# Safety_Thermocouple_Interface_-_MCU.net
KiCad netlist of a schematic drawn in Altium Designer
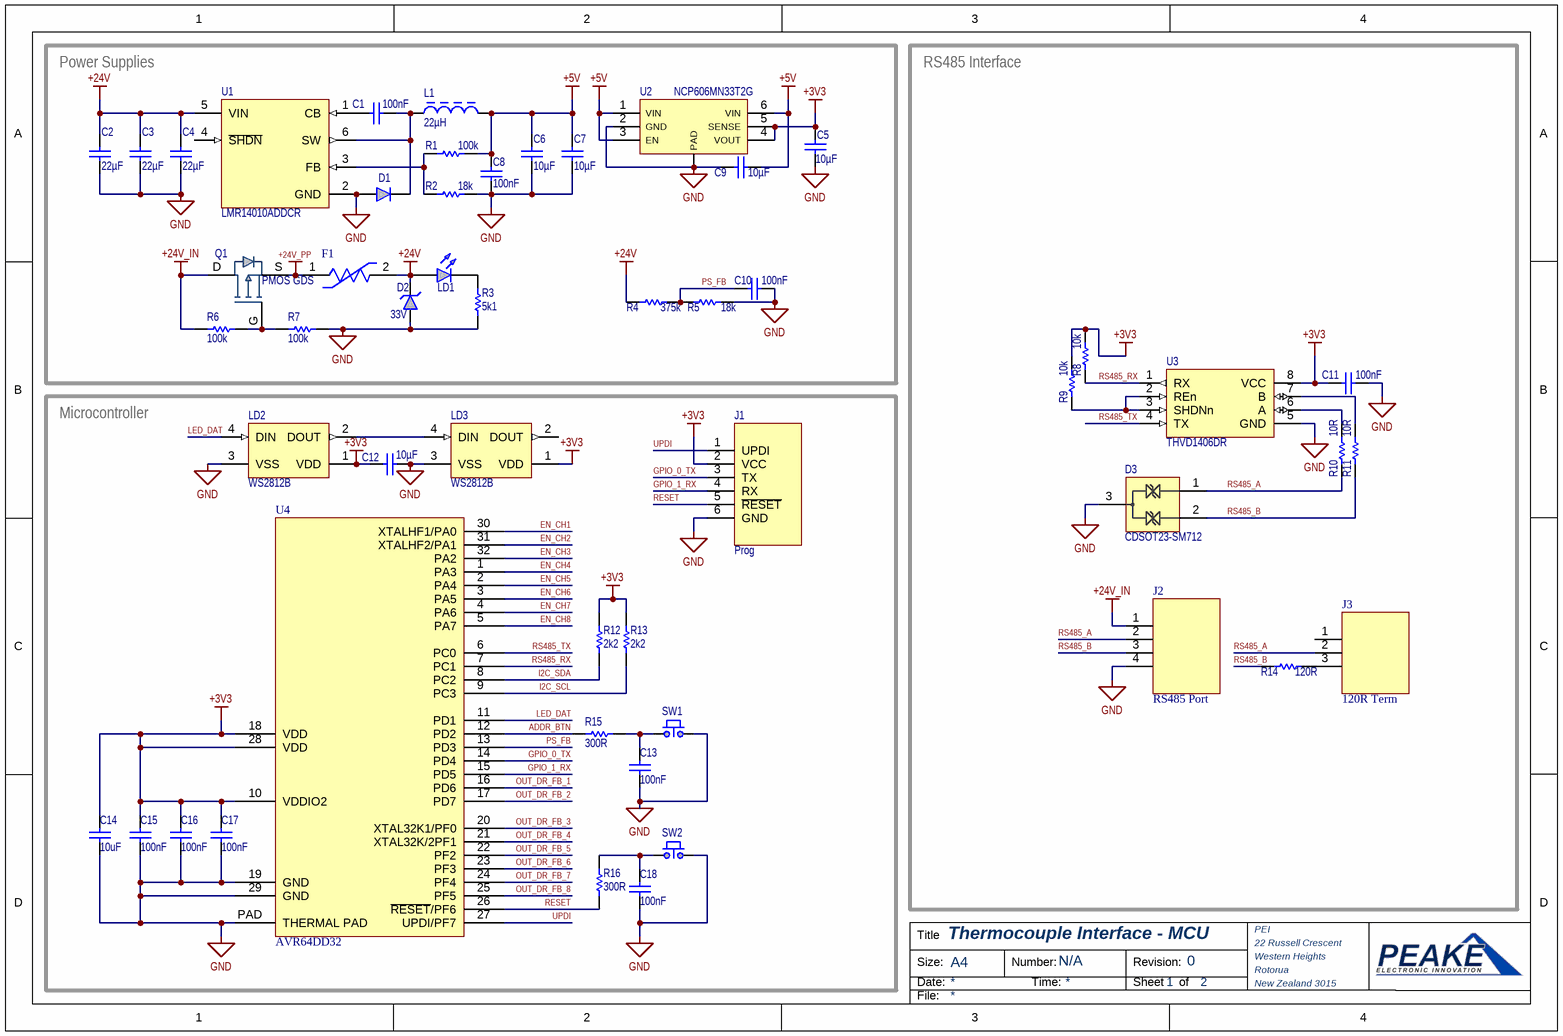
[diagram p0: Safety Thermocouple Interface - MCU.SchDoc]

(export (version "E")
  (design (tool "Eeschema 10.0.6"))
  (components
    (comp (ref "C1")
      (value "100nF")
      (footprint "0603_CAP")
      (description "SMD Capacitor")
      (fields (field (name "Comment") "Capacitor"))
      (libsource (lib "Scion Research") (part "CMP-019-00005-2"))
    )
    (comp (ref "C2")
      (value "22µF")
      (footprint "1206_CAP")
      (description "SMD Capacitor")
      (fields (field (name "Comment") "Capacitor"))
      (libsource (lib "Scion Research") (part "CMP-019-00005-2"))
    )
    (comp (ref "C3")
      (value "22µF")
      (footprint "1206_CAP")
      (description "SMD Capacitor")
      (fields (field (name "Comment") "Capacitor"))
      (libsource (lib "Scion Research") (part "CMP-019-00005-2"))
    )
    (comp (ref "C4")
      (value "22µF")
      (footprint "1206_CAP")
      (description "SMD Capacitor")
      (fields (field (name "Comment") "Capacitor"))
      (libsource (lib "Scion Research") (part "CMP-019-00005-2"))
    )
    (comp (ref "C5")
      (value "10µF")
      (footprint "0603_CAP")
      (description "SMD Capacitor")
      (fields (field (name "Comment") "Capacitor"))
      (libsource (lib "Scion Research") (part "CMP-019-00005-2"))
    )
    (comp (ref "C6")
      (value "10µF")
      (footprint "0603_CAP")
      (description "SMD Capacitor")
      (fields (field (name "Comment") "Capacitor"))
      (libsource (lib "Scion Research") (part "CMP-019-00005-2"))
    )
    (comp (ref "C7")
      (value "10µF")
      (footprint "0603_CAP")
      (description "SMD Capacitor")
      (fields (field (name "Comment") "Capacitor"))
      (libsource (lib "Scion Research") (part "CMP-019-00005-2"))
    )
    (comp (ref "C8")
      (value "100nF")
      (footprint "0603_CAP")
      (description "SMD Capacitor")
      (fields (field (name "Comment") "Capacitor"))
      (libsource (lib "Scion Research") (part "CMP-019-00005-2"))
    )
    (comp (ref "C9")
      (value "10µF")
      (footprint "0603_CAP")
      (description "SMD Capacitor")
      (fields (field (name "Comment") "Capacitor"))
      (libsource (lib "Scion Research") (part "CMP-019-00005-2"))
    )
    (comp (ref "C10")
      (value "100nF")
      (footprint "0603_CAP")
      (description "SMD Capacitor")
      (fields (field (name "Comment") "Capacitor"))
      (libsource (lib "Scion Research") (part "CMP-019-00005-2"))
    )
    (comp (ref "C11")
      (value "100nF")
      (footprint "0603_CAP")
      (description "SMD Capacitor")
      (fields (field (name "Comment") "Capacitor"))
      (libsource (lib "Scion Research") (part "CMP-019-00005-2"))
    )
    (comp (ref "C12")
      (value "10µF")
      (footprint "0603_CAP")
      (description "SMD Capacitor")
      (fields (field (name "Comment") "Capacitor"))
      (libsource (lib "Scion Research") (part "CMP-019-00005-2"))
    )
    (comp (ref "C13")
      (value "100nF")
      (footprint "0603_CAP")
      (description "SMD Capacitor")
      (fields (field (name "Comment") "Capacitor"))
      (libsource (lib "Scion Research") (part "CMP-019-00005-2"))
    )
    (comp (ref "C14")
      (value "10uF")
      (footprint "0603_CAP")
      (description "SMD Capacitor")
      (fields (field (name "Comment") "Capacitor"))
      (libsource (lib "Scion Research") (part "CMP-019-00005-2"))
    )
    (comp (ref "C15")
      (value "100nF")
      (footprint "0603_CAP")
      (description "SMD Capacitor")
      (fields (field (name "Comment") "Capacitor"))
      (libsource (lib "Scion Research") (part "CMP-019-00005-2"))
    )
    (comp (ref "C16")
      (value "100nF")
      (footprint "0603_CAP")
      (description "SMD Capacitor")
      (fields (field (name "Comment") "Capacitor"))
      (libsource (lib "Scion Research") (part "CMP-019-00005-2"))
    )
    (comp (ref "C17")
      (value "100nF")
      (footprint "0603_CAP")
      (description "SMD Capacitor")
      (fields (field (name "Comment") "Capacitor"))
      (libsource (lib "Scion Research") (part "CMP-019-00005-2"))
    )
    (comp (ref "C18")
      (value "100nF")
      (footprint "0603_CAP")
      (description "SMD Capacitor")
      (fields (field (name "Comment") "Capacitor"))
      (libsource (lib "Scion Research") (part "CMP-019-00005-2"))
    )
    (comp (ref "D1")
      (value "Diode")
      (footprint "SOD-123")
      (description "SMD Diode")
      (libsource (lib "Scion Research") (part "Diode"))
    )
    (comp (ref "D2")
      (value "Transil")
      (footprint "SMBJ")
      (description "Transient Voltage Suppressor")
      (fields (field (name "RATED VOLTAGE") "33V"))
      (libsource (lib "Scion Research") (part "CMP-004-0042-1"))
    )
    (comp (ref "D3")
      (value "CDSOT23-SM712")
      (footprint "FP-SOT23-IPC_C")
      (description "Trans Voltage Suppressor Diode, 400W, 7V V(RWM), Bidirectional, 2 Element, Silicon")
      (libsource (lib "Scion Research") (part "CDSOT23-SM712"))
    )
    (comp (ref "F1")
      (value "0ZCF0100AF2A")
      (footprint "FP-0ZCF0100AF2A-MFG")
      (description "PTC Resettable Fuse 100A 0.5s 60VDC 0.09 Ohm 2-Pin 2920 T/R")
      (libsource (lib "Scion Research") (part "CMP-00051-1"))
    )
    (comp (ref "J1")
      (value "Prog")
      (footprint "DIP6")
      (description "6 Pin Connector")
      (libsource (lib "Scion Research") (part "CMP-002-00081-5"))
    )
    (comp (ref "J2")
      (value "RS485 Port")
      (footprint "4_Pin  DB2EVC-3.81-4P-GN LCSC version")
      (description "4 Pin Connector")
      (libsource (lib "Scion Research") (part "CMP-002-00078-6"))
    )
    (comp (ref "J3")
      (value "120R Term")
      (footprint "SIP3")
      (description "3 Pin Connector")
      (libsource (lib "Scion Research") (part "CMP-002-00075-6"))
    )
    (comp (ref "L1")
      (value "22µH")
      (footprint "BOUR-SRN8040_V")
      (description "Power Inductor")
      (fields (field (name "Comment") "Inductor"))
      (libsource (lib "Scion Research") (part "Inductor"))
    )
    (comp (ref "LD1")
      (value "LED")
      (footprint "0805")
      (description "SMD LED")
      (libsource (lib "Scion Research") (part "CMP-004-00032-1"))
    )
    (comp (ref "LD2")
      (value "WS2812B")
      (footprint "WS2812B-2020")
      (fields (field (name "MANUFACTURER") "Adafruit Industries"))
      (libsource (lib "Scion Research") (part "CMP-007-00035-3"))
    )
    (comp (ref "LD3")
      (value "WS2812B")
      (footprint "WS2812B-2020")
      (fields (field (name "MANUFACTURER") "Adafruit Industries"))
      (libsource (lib "Scion Research") (part "CMP-007-00035-3"))
    )
    (comp (ref "Q1")
      (value "PMOS GDS")
      (footprint "PowerDI 5060-8")
      (description "P Channel MOSFET")
      (libsource (lib "Scion Research") (part "CMP-004-0035-2"))
    )
    (comp (ref "R1")
      (value "Resistor")
      (footprint "0603_RES")
      (description "SMD Resistor")
      (fields (field (name "ALTIUM_VALUE") "100k"))
      (libsource (lib "Scion Research") (part "CMP-009-00177-2"))
    )
    (comp (ref "R2")
      (value "Resistor")
      (footprint "0603_RES")
      (description "SMD Resistor")
      (fields (field (name "ALTIUM_VALUE") "18k"))
      (libsource (lib "Scion Research") (part "CMP-009-00177-2"))
    )
    (comp (ref "R3")
      (value "Resistor")
      (footprint "0603_RES")
      (description "SMD Resistor")
      (fields (field (name "ALTIUM_VALUE") "5k1"))
      (libsource (lib "Scion Research") (part "CMP-009-00177-2"))
    )
    (comp (ref "R4")
      (value "Resistor")
      (footprint "0603_RES")
      (description "SMD Resistor")
      (fields (field (name "ALTIUM_VALUE") "375k"))
      (libsource (lib "Scion Research") (part "CMP-009-00177-2"))
    )
    (comp (ref "R5")
      (value "Resistor")
      (footprint "0603_RES")
      (description "SMD Resistor")
      (fields (field (name "ALTIUM_VALUE") "18k"))
      (libsource (lib "Scion Research") (part "CMP-009-00177-2"))
    )
    (comp (ref "R6")
      (value "Resistor")
      (footprint "0603_RES")
      (description "SMD Resistor")
      (fields (field (name "ALTIUM_VALUE") "100k"))
      (libsource (lib "Scion Research") (part "CMP-009-00177-2"))
    )
    (comp (ref "R7")
      (value "Resistor")
      (footprint "0603_RES")
      (description "SMD Resistor")
      (fields (field (name "ALTIUM_VALUE") "100k"))
      (libsource (lib "Scion Research") (part "CMP-009-00177-2"))
    )
    (comp (ref "R8")
      (value "Resistor")
      (footprint "0603_RES")
      (description "SMD Resistor")
      (fields (field (name "ALTIUM_VALUE") "10k"))
      (libsource (lib "Scion Research") (part "CMP-009-00177-2"))
    )
    (comp (ref "R9")
      (value "Resistor")
      (footprint "0603_RES")
      (description "SMD Resistor")
      (fields (field (name "ALTIUM_VALUE") "10k"))
      (libsource (lib "Scion Research") (part "CMP-009-00177-2"))
    )
    (comp (ref "R10")
      (value "Resistor")
      (footprint "0603_RES")
      (description "SMD Resistor")
      (fields (field (name "ALTIUM_VALUE") "10R"))
      (libsource (lib "Scion Research") (part "CMP-009-00177-2"))
    )
    (comp (ref "R11")
      (value "Resistor")
      (footprint "0603_RES")
      (description "SMD Resistor")
      (fields (field (name "ALTIUM_VALUE") "10R"))
      (libsource (lib "Scion Research") (part "CMP-009-00177-2"))
    )
    (comp (ref "R12")
      (value "Resistor")
      (footprint "0603_RES")
      (description "SMD Resistor")
      (fields (field (name "ALTIUM_VALUE") "2k2"))
      (libsource (lib "Scion Research") (part "CMP-009-00177-2"))
    )
    (comp (ref "R13")
      (value "Resistor")
      (footprint "0603_RES")
      (description "SMD Resistor")
      (fields (field (name "ALTIUM_VALUE") "2k2"))
      (libsource (lib "Scion Research") (part "CMP-009-00177-2"))
    )
    (comp (ref "R14")
      (value "Resistor")
      (footprint "0603_RES")
      (description "SMD Resistor")
      (fields (field (name "ALTIUM_VALUE") "120R"))
      (libsource (lib "Scion Research") (part "CMP-009-00177-2"))
    )
    (comp (ref "R15")
      (value "Resistor")
      (footprint "0603_RES")
      (description "SMD Resistor")
      (fields (field (name "ALTIUM_VALUE") "300R"))
      (libsource (lib "Scion Research") (part "CMP-009-00177-2"))
    )
    (comp (ref "R16")
      (value "Resistor")
      (footprint "0603_RES")
      (description "SMD Resistor")
      (fields (field (name "ALTIUM_VALUE") "300R"))
      (libsource (lib "Scion Research") (part "CMP-009-00177-2"))
    )
    (comp (ref "SW1")
      (value "EVP-AAN02Q")
      (footprint "FP-EVP-AAN02Q-MFG")
      (description "Switch Tactile N.O. SPST Rectangular Button J-Bend 0.02A 15VDC 100000Cycles 5N SMD T/R")
      (libsource (lib "Scion Research") (part "67890d47754ac483cb1d3ba3be74b6c"))
    )
    (comp (ref "SW2")
      (value "EVP-AAN02Q")
      (footprint "FP-EVP-AAN02Q-MFG")
      (description "Switch Tactile N.O. SPST Rectangular Button J-Bend 0.02A 15VDC 100000Cycles 5N SMD T/R")
      (libsource (lib "Scion Research") (part "67890d47754ac483cb1d3ba3be74b6c"))
    )
    (comp (ref "U1")
      (value "LMR14010ADDCR")
      (footprint "FP-DDC0006A-IPC_A")
      (description "7-40VDC-DC buck converter")
      (libsource (lib "Scion Research") (part "LMR14010"))
    )
    (comp (ref "U2")
      (value "NCP606MN33T2G")
      (footprint "QFN95P330X295X100_HS-7N")
      (description "Fixed Positive LDO Regulator, 3.3V, 0.22V Dropout, CMOS")
      (libsource (lib "Scion Research") (part "NCP606MN33T2G-Symbol-1"))
    )
    (comp (ref "U3")
      (value "THVD1406DR")
      (footprint "SOIC127P600X175-8N")
      (description "Line Transceiver, 1 Func, 1 Driver, 1 Rcvr, PDSO8")
      (libsource (lib "Scion Research") (part "THVD1406DR-Symbol-1"))
    )
    (comp (ref "U4")
      (value "AVR64DD32")
      (footprint "32P VQFN")
      (libsource (lib "Scion Research") (part "AVR64DD32"))
    )
  )
  (nets
    (net (code "1") (name "+3V3") (class "Default")
      (node (ref "C11") (pin "2") (pinfunction "2_2") (pintype "passive"))
      (node (ref "C12") (pin "2") (pinfunction "2_2") (pintype "passive"))
      (node (ref "C14") (pin "2") (pinfunction "2_2") (pintype "passive"))
      (node (ref "C15") (pin "2") (pinfunction "2_2") (pintype "passive"))
      (node (ref "C16") (pin "2") (pinfunction "2_2") (pintype "passive"))
      (node (ref "C17") (pin "2") (pinfunction "2_2") (pintype "passive"))
      (node (ref "C5") (pin "1") (pinfunction "1_1") (pintype "passive"))
      (node (ref "J1") (pin "2") (pinfunction "VCC_2") (pintype "passive"))
      (node (ref "LD2") (pin "1") (pinfunction "VDD_1") (pintype "power_in"))
      (node (ref "LD3") (pin "1") (pinfunction "VDD_1") (pintype "power_in"))
      (node (ref "R12") (pin "1") (pinfunction "1_1") (pintype "passive"))
      (node (ref "R13") (pin "1") (pinfunction "1_1") (pintype "passive"))
      (node (ref "R8") (pin "1") (pinfunction "1_1") (pintype "passive"))
      (node (ref "R9") (pin "1") (pinfunction "1_1") (pintype "passive"))
      (node (ref "U2") (pin "4") (pinfunction "VOUT_4") (pintype "passive"))
      (node (ref "U2") (pin "5") (pinfunction "SENSE_5") (pintype "passive"))
      (node (ref "U3") (pin "8") (pinfunction "VCC_8") (pintype "power_in"))
      (node (ref "U4") (pin "10") (pinfunction "VDDIO2_10") (pintype "passive"))
      (node (ref "U4") (pin "18") (pinfunction "VDD_18") (pintype "passive"))
      (node (ref "U4") (pin "28") (pinfunction "VDD_28") (pintype "passive"))
    )
    (net (code "2") (name "+5V") (class "Default")
      (node (ref "C6") (pin "1") (pinfunction "1_1") (pintype "passive"))
      (node (ref "C7") (pin "1") (pinfunction "1_1") (pintype "passive"))
      (node (ref "C8") (pin "1") (pinfunction "1_1") (pintype "passive"))
      (node (ref "C9") (pin "1") (pinfunction "1_1") (pintype "passive"))
      (node (ref "L1") (pin "2") (pinfunction "2_2") (pintype "passive"))
      (node (ref "R1") (pin "2") (pinfunction "2_2") (pintype "passive"))
      (node (ref "U2") (pin "1") (pinfunction "VIN_1") (pintype "passive"))
      (node (ref "U2") (pin "3") (pinfunction "EN_3") (pintype "passive"))
      (node (ref "U2") (pin "6") (pinfunction "VIN_6") (pintype "passive"))
    )
    (net (code "3") (name "+24V") (class "Default")
      (node (ref "C2") (pin "1") (pinfunction "1_1") (pintype "passive"))
      (node (ref "C3") (pin "1") (pinfunction "1_1") (pintype "passive"))
      (node (ref "C4") (pin "1") (pinfunction "1_1") (pintype "passive"))
      (node (ref "D2") (pin "2") (pinfunction "K_2") (pintype "passive"))
      (node (ref "F1") (pin "2") (pinfunction "2_2") (pintype "passive"))
      (node (ref "LD1") (pin "2") (pinfunction "A_2") (pintype "passive"))
      (node (ref "R4") (pin "1") (pinfunction "1_1") (pintype "passive"))
      (node (ref "U1") (pin "5") (pinfunction "VIN_5") (pintype "power_in"))
    )
    (net (code "4") (name "+24V_IN") (class "Default")
      (node (ref "J2") (pin "1") (pinfunction "1_1") (pintype "passive"))
      (node (ref "Q1") (pin "D") (pinfunction "D_D") (pintype "passive"))
      (node (ref "R6") (pin "1") (pinfunction "1_1") (pintype "passive"))
    )
    (net (code "5") (name "+24V_PP") (class "Default")
      (node (ref "F1") (pin "1") (pinfunction "1_1") (pintype "passive"))
      (node (ref "Q1") (pin "S") (pinfunction "S_S") (pintype "passive"))
    )
    (net (code "6") (name "/ADDR_BTN") (class "Default")
      (node (ref "R15") (pin "2") (pinfunction "2_2") (pintype "passive"))
      (node (ref "U4") (pin "12") (pinfunction "PD2_12") (pintype "passive"))
    )
    (net (code "7") (name "/EN_CH1") (class "Default")
      (node (ref "U4") (pin "30") (pinfunction "XTALHF1/PA0_30") (pintype "passive"))
    )
    (net (code "8") (name "/EN_CH2") (class "Default")
      (node (ref "U4") (pin "31") (pinfunction "XTALHF2/PA1_31") (pintype "passive"))
    )
    (net (code "9") (name "/EN_CH3") (class "Default")
      (node (ref "U4") (pin "32") (pinfunction "PA2_32") (pintype "passive"))
    )
    (net (code "10") (name "/EN_CH4") (class "Default")
      (node (ref "U4") (pin "1") (pinfunction "PA3_1") (pintype "passive"))
    )
    (net (code "11") (name "/EN_CH5") (class "Default")
      (node (ref "U4") (pin "2") (pinfunction "PA4_2") (pintype "passive"))
    )
    (net (code "12") (name "/EN_CH6") (class "Default")
      (node (ref "U4") (pin "3") (pinfunction "PA5_3") (pintype "passive"))
    )
    (net (code "13") (name "/EN_CH7") (class "Default")
      (node (ref "U4") (pin "4") (pinfunction "PA6_4") (pintype "passive"))
    )
    (net (code "14") (name "/EN_CH8") (class "Default")
      (node (ref "U4") (pin "5") (pinfunction "PA7_5") (pintype "passive"))
    )
    (net (code "15") (name "/GPIO_0_TX") (class "Default")
      (node (ref "J1") (pin "3") (pinfunction "TX_3") (pintype "passive"))
      (node (ref "U4") (pin "14") (pinfunction "PD4_14") (pintype "passive"))
    )
    (net (code "16") (name "/GPIO_1_RX") (class "Default")
      (node (ref "J1") (pin "4") (pinfunction "RX_4") (pintype "passive"))
      (node (ref "U4") (pin "15") (pinfunction "PD5_15") (pintype "passive"))
    )
    (net (code "17") (name "/I2C_SCL") (class "Default")
      (node (ref "R13") (pin "2") (pinfunction "2_2") (pintype "passive"))
      (node (ref "U4") (pin "9") (pinfunction "PC3_9") (pintype "passive"))
    )
    (net (code "18") (name "/I2C_SDA") (class "Default")
      (node (ref "R12") (pin "2") (pinfunction "2_2") (pintype "passive"))
      (node (ref "U4") (pin "8") (pinfunction "PC2_8") (pintype "passive"))
    )
    (net (code "19") (name "/LED_DAT") (class "Default")
      (node (ref "LD2") (pin "4") (pinfunction "DIN_4") (pintype "input"))
      (node (ref "U4") (pin "11") (pinfunction "PD1_11") (pintype "passive"))
    )
    (net (code "20") (name "/OUT_DR_FB_1") (class "Default")
      (node (ref "U4") (pin "16") (pinfunction "PD6_16") (pintype "passive"))
    )
    (net (code "21") (name "/OUT_DR_FB_2") (class "Default")
      (node (ref "U4") (pin "17") (pinfunction "PD7_17") (pintype "passive"))
    )
    (net (code "22") (name "/OUT_DR_FB_3") (class "Default")
      (node (ref "U4") (pin "20") (pinfunction "XTAL32K1/PF0_20") (pintype "passive"))
    )
    (net (code "23") (name "/OUT_DR_FB_4") (class "Default")
      (node (ref "U4") (pin "21") (pinfunction "XTAL32K/2PF1_21") (pintype "passive"))
    )
    (net (code "24") (name "/OUT_DR_FB_5") (class "Default")
      (node (ref "U4") (pin "22") (pinfunction "PF2_22") (pintype "passive"))
    )
    (net (code "25") (name "/OUT_DR_FB_6") (class "Default")
      (node (ref "U4") (pin "23") (pinfunction "PF3_23") (pintype "passive"))
    )
    (net (code "26") (name "/OUT_DR_FB_7") (class "Default")
      (node (ref "U4") (pin "24") (pinfunction "PF4_24") (pintype "passive"))
    )
    (net (code "27") (name "/OUT_DR_FB_8") (class "Default")
      (node (ref "U4") (pin "25") (pinfunction "PF5_25") (pintype "passive"))
    )
    (net (code "28") (name "/PS_FB") (class "Default")
      (node (ref "C10") (pin "1") (pinfunction "1_1") (pintype "passive"))
      (node (ref "R4") (pin "2") (pinfunction "2_2") (pintype "passive"))
      (node (ref "R5") (pin "2") (pinfunction "2_2") (pintype "passive"))
      (node (ref "U4") (pin "13") (pinfunction "PD3_13") (pintype "passive"))
    )
    (net (code "29") (name "/RESET") (class "Default")
      (node (ref "J1") (pin "5") (pinfunction "~{RESET}_5") (pintype "passive"))
      (node (ref "R16") (pin "1") (pinfunction "1_1") (pintype "passive"))
      (node (ref "U4") (pin "26") (pinfunction "~{RESET}/PF6_26") (pintype "passive"))
    )
    (net (code "30") (name "/RS485_A") (class "Default")
      (node (ref "D3") (pin "1") (pinfunction "1_1") (pintype "passive"))
      (node (ref "J2") (pin "2") (pinfunction "2_2") (pintype "passive"))
      (node (ref "J3") (pin "2") (pinfunction "2_2") (pintype "passive"))
      (node (ref "R10") (pin "1") (pinfunction "1_1") (pintype "passive"))
    )
    (net (code "31") (name "/RS485_B") (class "Default")
      (node (ref "D3") (pin "2") (pinfunction "2_2") (pintype "passive"))
      (node (ref "J2") (pin "3") (pinfunction "3_3") (pintype "passive"))
      (node (ref "R11") (pin "1") (pinfunction "1_1") (pintype "passive"))
      (node (ref "R14") (pin "1") (pinfunction "1_1") (pintype "passive"))
    )
    (net (code "32") (name "/RS485_RX") (class "Default")
      (node (ref "R8") (pin "2") (pinfunction "2_2") (pintype "passive"))
      (node (ref "U3") (pin "1") (pinfunction "RX_1") (pintype "output"))
      (node (ref "U4") (pin "7") (pinfunction "PC1_7") (pintype "passive"))
    )
    (net (code "33") (name "/RS485_TX") (class "Default")
      (node (ref "U3") (pin "4") (pinfunction "TX_4") (pintype "input"))
      (node (ref "U4") (pin "6") (pinfunction "PC0_6") (pintype "passive"))
    )
    (net (code "34") (name "/UPDI") (class "Default")
      (node (ref "J1") (pin "1") (pinfunction "UPDI_1") (pintype "passive"))
      (node (ref "U4") (pin "27") (pinfunction "UPDI/PF7_27") (pintype "passive"))
    )
    (net (code "35") (name "GND") (class "Default")
      (node (ref "C10") (pin "2") (pinfunction "2_2") (pintype "passive"))
      (node (ref "C11") (pin "1") (pinfunction "1_1") (pintype "passive"))
      (node (ref "C12") (pin "1") (pinfunction "1_1") (pintype "passive"))
      (node (ref "C13") (pin "1") (pinfunction "1_1") (pintype "passive"))
      (node (ref "C14") (pin "1") (pinfunction "1_1") (pintype "passive"))
      (node (ref "C15") (pin "1") (pinfunction "1_1") (pintype "passive"))
      (node (ref "C16") (pin "1") (pinfunction "1_1") (pintype "passive"))
      (node (ref "C17") (pin "1") (pinfunction "1_1") (pintype "passive"))
      (node (ref "C18") (pin "1") (pinfunction "1_1") (pintype "passive"))
      (node (ref "C2") (pin "2") (pinfunction "2_2") (pintype "passive"))
      (node (ref "C3") (pin "2") (pinfunction "2_2") (pintype "passive"))
      (node (ref "C4") (pin "2") (pinfunction "2_2") (pintype "passive"))
      (node (ref "C5") (pin "2") (pinfunction "2_2") (pintype "passive"))
      (node (ref "C6") (pin "2") (pinfunction "2_2") (pintype "passive"))
      (node (ref "C7") (pin "2") (pinfunction "2_2") (pintype "passive"))
      (node (ref "C8") (pin "2") (pinfunction "2_2") (pintype "passive"))
      (node (ref "C9") (pin "2") (pinfunction "2_2") (pintype "passive"))
      (node (ref "D1") (pin "2") (pinfunction "A_2") (pintype "passive"))
      (node (ref "D2") (pin "1") (pinfunction "A_1") (pintype "passive"))
      (node (ref "D3") (pin "3") (pinfunction "3_3") (pintype "passive"))
      (node (ref "J1") (pin "6") (pinfunction "GND_6") (pintype "passive"))
      (node (ref "J2") (pin "4") (pinfunction "4_4") (pintype "passive"))
      (node (ref "LD2") (pin "3") (pinfunction "VSS_3") (pintype "power_in"))
      (node (ref "LD3") (pin "3") (pinfunction "VSS_3") (pintype "power_in"))
      (node (ref "R2") (pin "2") (pinfunction "2_2") (pintype "passive"))
      (node (ref "R3") (pin "2") (pinfunction "2_2") (pintype "passive"))
      (node (ref "R5") (pin "1") (pinfunction "1_1") (pintype "passive"))
      (node (ref "R7") (pin "2") (pinfunction "2_2") (pintype "passive"))
      (node (ref "SW1") (pin "2") (pinfunction "2_2") (pintype "passive"))
      (node (ref "SW2") (pin "2") (pinfunction "2_2") (pintype "passive"))
      (node (ref "U1") (pin "2") (pinfunction "GND_2") (pintype "power_in"))
      (node (ref "U2") (pin "2") (pinfunction "GND_2") (pintype "passive"))
      (node (ref "U2") (pin "PAD") (pinfunction "PAD_PAD") (pintype "passive"))
      (node (ref "U3") (pin "5") (pinfunction "GND_5") (pintype "power_in"))
      (node (ref "U4") (pin "19") (pinfunction "GND_19") (pintype "passive"))
      (node (ref "U4") (pin "29") (pinfunction "GND_29") (pintype "passive"))
      (node (ref "U4") (pin "PAD") (pinfunction "THERMAL_PAD_PAD") (pintype "passive"))
    )
    (net (code "36") (name "Net-(C13-Pad2)") (class "Default")
      (node (ref "C13") (pin "2") (pinfunction "2_2") (pintype "passive"))
      (node (ref "R15") (pin "1") (pinfunction "1_1") (pintype "passive"))
      (node (ref "SW1") (pin "1") (pinfunction "1_1") (pintype "passive"))
    )
    (net (code "37") (name "Net-(C18-Pad2)") (class "Default")
      (node (ref "C18") (pin "2") (pinfunction "2_2") (pintype "passive"))
      (node (ref "R16") (pin "2") (pinfunction "2_2") (pintype "passive"))
      (node (ref "SW2") (pin "1") (pinfunction "1_1") (pintype "passive"))
    )
    (net (code "38") (name "Net-(D1-K)") (class "Default")
      (node (ref "C1") (pin "1") (pinfunction "1_1") (pintype "passive"))
      (node (ref "D1") (pin "1") (pinfunction "K_1") (pintype "passive"))
      (node (ref "L1") (pin "1") (pinfunction "1_1") (pintype "passive"))
      (node (ref "U1") (pin "6") (pinfunction "SW_6") (pintype "output"))
    )
    (net (code "39") (name "Net-(J3-Pad3)") (class "Default")
      (node (ref "J3") (pin "3") (pinfunction "3_3") (pintype "passive"))
      (node (ref "R14") (pin "2") (pinfunction "2_2") (pintype "passive"))
    )
    (net (code "40") (name "Net-(LD1-K)") (class "Default")
      (node (ref "LD1") (pin "1") (pinfunction "K_1") (pintype "passive"))
      (node (ref "R3") (pin "1") (pinfunction "1_1") (pintype "passive"))
    )
    (net (code "41") (name "Net-(LD2-DOUT)") (class "Default")
      (node (ref "LD2") (pin "2") (pinfunction "DOUT_2") (pintype "output"))
      (node (ref "LD3") (pin "4") (pinfunction "DIN_4") (pintype "input"))
    )
    (net (code "42") (name "Net-(Q1-PadG)") (class "Default")
      (node (ref "Q1") (pin "G") (pinfunction "G_G") (pintype "passive"))
      (node (ref "R6") (pin "2") (pinfunction "2_2") (pintype "passive"))
      (node (ref "R7") (pin "1") (pinfunction "1_1") (pintype "passive"))
    )
    (net (code "43") (name "Net-(U1-CB)") (class "Default")
      (node (ref "C1") (pin "2") (pinfunction "2_2") (pintype "passive"))
      (node (ref "U1") (pin "1") (pinfunction "CB_1") (pintype "input"))
    )
    (net (code "44") (name "Net-(U1-FB)") (class "Default")
      (node (ref "R1") (pin "1") (pinfunction "1_1") (pintype "passive"))
      (node (ref "R2") (pin "1") (pinfunction "1_1") (pintype "passive"))
      (node (ref "U1") (pin "3") (pinfunction "FB_3") (pintype "input"))
    )
    (net (code "45") (name "Net-(U3-A)") (class "Default")
      (node (ref "R10") (pin "2") (pinfunction "2_2") (pintype "passive"))
      (node (ref "U3") (pin "6") (pinfunction "A_6") (pintype "bidirectional"))
    )
    (net (code "46") (name "Net-(U3-B)") (class "Default")
      (node (ref "R11") (pin "2") (pinfunction "2_2") (pintype "passive"))
      (node (ref "U3") (pin "7") (pinfunction "B_7") (pintype "bidirectional"))
    )
    (net (code "47") (name "Net-(U3-REn)") (class "Default")
      (node (ref "R9") (pin "2") (pinfunction "2_2") (pintype "passive"))
      (node (ref "U3") (pin "2") (pinfunction "REn_2") (pintype "input"))
      (node (ref "U3") (pin "3") (pinfunction "SHDNn_3") (pintype "input"))
    )
    (net (code "48") (name "unconnected-(J3-Pad1)") (class "Default")
      (node (ref "J3") (pin "1") (pinfunction "1_1") (pintype "passive"))
    )
    (net (code "49") (name "unconnected-(LD3-DOUT-Pad2)") (class "Default")
      (node (ref "LD3") (pin "2") (pinfunction "DOUT_2") (pintype "output"))
    )
    (net (code "50") (name "unconnected-(U1-~{SHDN}-Pad4)") (class "Default")
      (node (ref "U1") (pin "4") (pinfunction "~{SHDN}_4") (pintype "input"))
    )
  )
)
